# Daughter_Board.net
KiCad netlist of a schematic drawn in EAGLE
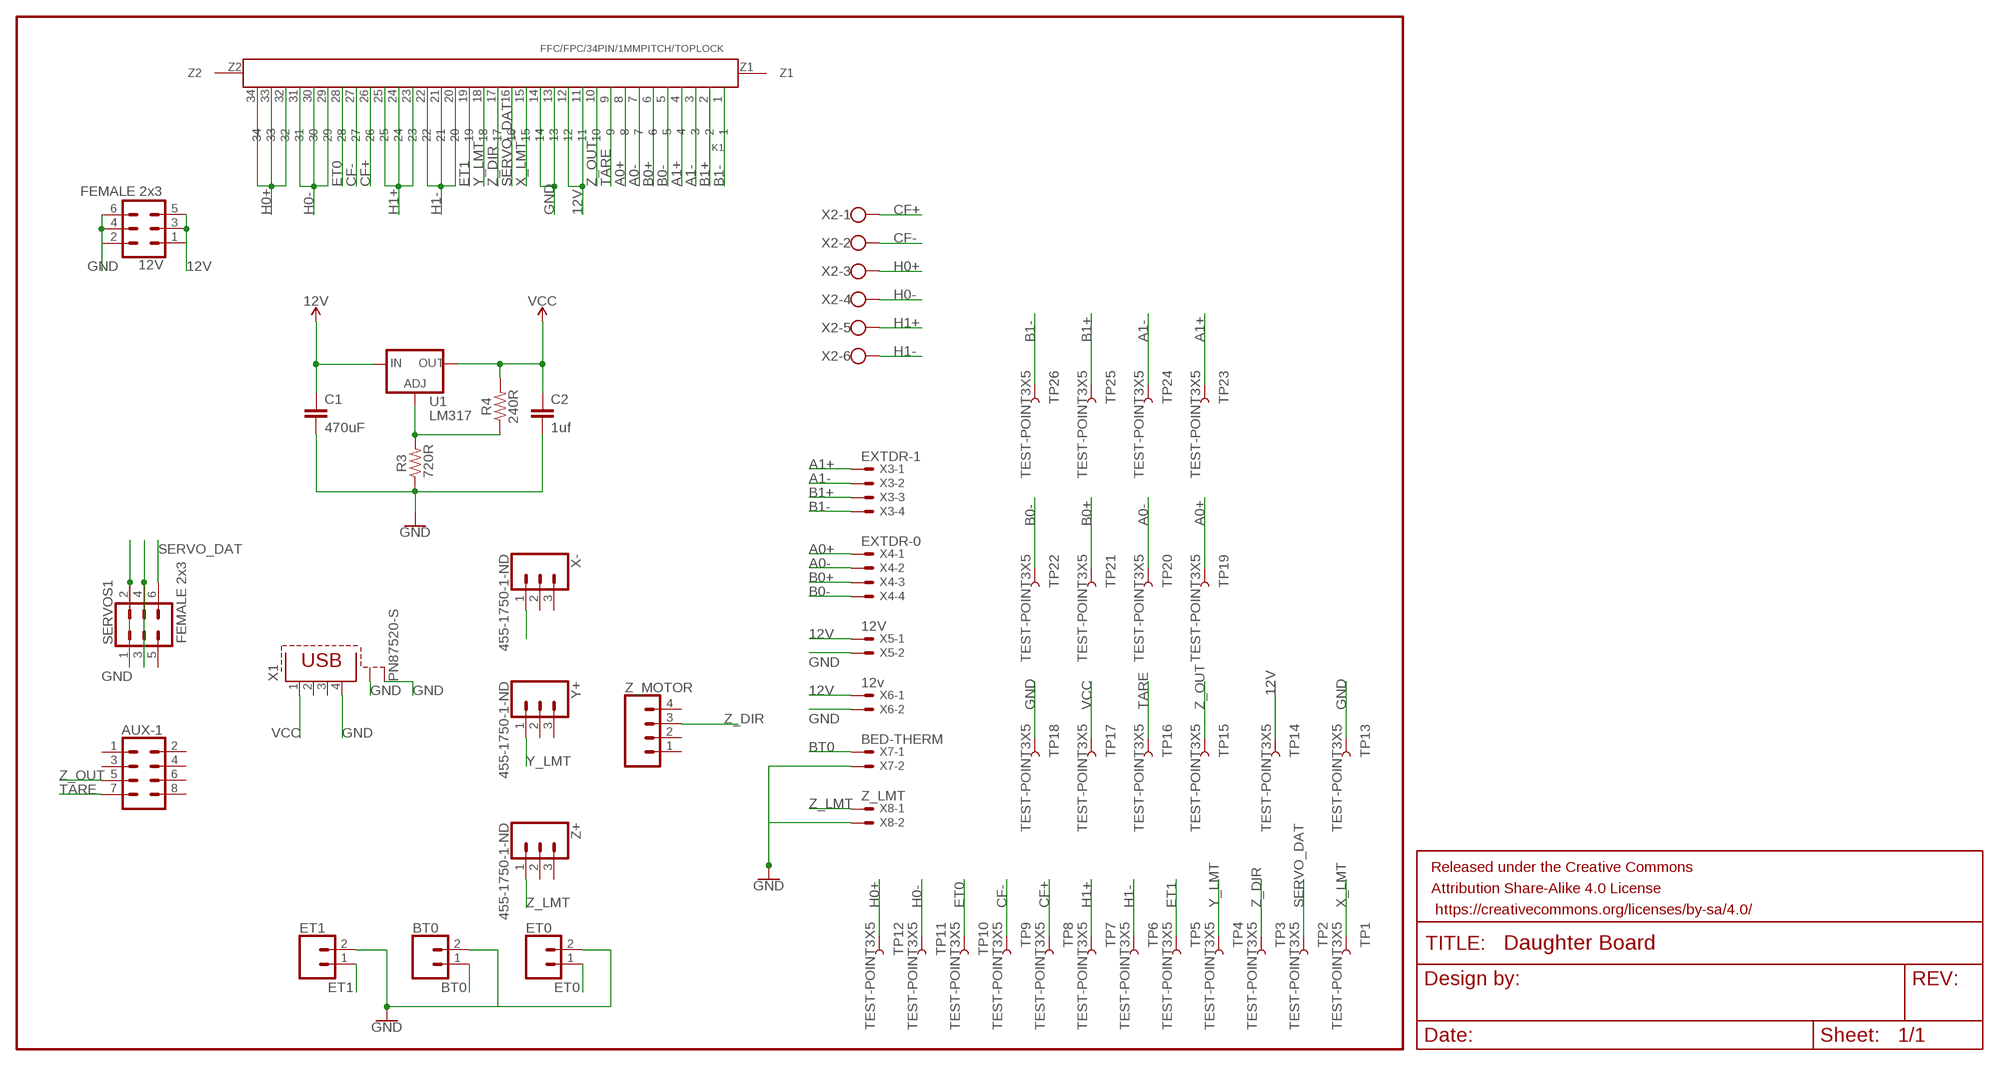
[diagram p0: schematic, sheet 1]

(export (version "E")
  (design (tool "Eeschema 10.0.6"))
  (components
    (comp (ref "12V")
      (value "FEMALE 2x3")
      (footprint "eagle-import:2X3")
      (libsource (lib "eagle-import") (part "CONN_03X2FEMALE"))
    )
    (comp (ref "AUX-1")
      (value "CONN_04X2")
      (footprint "eagle-import:2X4")
      (libsource (lib "eagle-import") (part "CONN_04X2"))
    )
    (comp (ref "BT0")
      (value "CONN_02")
      (footprint "eagle-import:1X02")
      (libsource (lib "eagle-import") (part "CONN_02"))
    )
    (comp (ref "C1")
      (value "470uF")
      (footprint "eagle-import:0603")
      (libsource (lib "eagle-import") (part "9.0PF-0603-50V-10%"))
    )
    (comp (ref "C2")
      (value "1uf")
      (footprint "eagle-import:0603")
      (libsource (lib "eagle-import") (part "9.0PF-0603-50V-10%"))
    )
    (comp (ref "ET0")
      (value "CONN_02")
      (footprint "eagle-import:1X02")
      (libsource (lib "eagle-import") (part "CONN_02"))
    )
    (comp (ref "ET1")
      (value "CONN_02")
      (footprint "eagle-import:1X02")
      (libsource (lib "eagle-import") (part "CONN_02"))
    )
    (comp (ref "FRAME1")
      (value "FRAME-LETTERNO_PACKAGE")
      (footprint "eagle-import:DUMMY")
      (fields (field (name "DESIGNER") "Nobody"))
      (libsource (lib "eagle-import") (part "FRAME-LETTERNO_PACKAGE"))
    )
    (comp (ref "K1")
      (value "FFC/FPC/34PIN/1MMPITCH/TOPLOCK")
      (footprint "eagle-import:34PIN_1MMPITCH_FFC_FPC")
      (libsource (lib "eagle-import") (part "FFC/FPC/34PIN/1MMPITCH/TOPLOCK"))
    )
    (comp (ref "R3")
      (value "720R")
      (footprint "eagle-import:0603")
      (libsource (lib "eagle-import") (part "RESISTOR0603"))
    )
    (comp (ref "R4")
      (value "240R")
      (footprint "eagle-import:0603")
      (libsource (lib "eagle-import") (part "RESISTOR0603"))
    )
    (comp (ref "SERVOS1")
      (value "FEMALE 2x3")
      (footprint "eagle-import:2X3")
      (libsource (lib "eagle-import") (part "CONN_03X2FEMALE"))
    )
    (comp (ref "TP1")
      (value "TEST-POINT3X5")
      (footprint "eagle-import:PAD.03X.05")
      (libsource (lib "eagle-import") (part "TEST-POINT3X5"))
    )
    (comp (ref "TP2")
      (value "TEST-POINT3X5")
      (footprint "eagle-import:PAD.03X.05")
      (libsource (lib "eagle-import") (part "TEST-POINT3X5"))
    )
    (comp (ref "TP3")
      (value "TEST-POINT3X5")
      (footprint "eagle-import:PAD.03X.05")
      (libsource (lib "eagle-import") (part "TEST-POINT3X5"))
    )
    (comp (ref "TP4")
      (value "TEST-POINT3X5")
      (footprint "eagle-import:PAD.03X.05")
      (libsource (lib "eagle-import") (part "TEST-POINT3X5"))
    )
    (comp (ref "TP5")
      (value "TEST-POINT3X5")
      (footprint "eagle-import:PAD.03X.05")
      (libsource (lib "eagle-import") (part "TEST-POINT3X5"))
    )
    (comp (ref "TP6")
      (value "TEST-POINT3X5")
      (footprint "eagle-import:PAD.03X.05")
      (libsource (lib "eagle-import") (part "TEST-POINT3X5"))
    )
    (comp (ref "TP7")
      (value "TEST-POINT3X5")
      (footprint "eagle-import:PAD.03X.05")
      (libsource (lib "eagle-import") (part "TEST-POINT3X5"))
    )
    (comp (ref "TP8")
      (value "TEST-POINT3X5")
      (footprint "eagle-import:PAD.03X.05")
      (libsource (lib "eagle-import") (part "TEST-POINT3X5"))
    )
    (comp (ref "TP9")
      (value "TEST-POINT3X5")
      (footprint "eagle-import:PAD.03X.05")
      (libsource (lib "eagle-import") (part "TEST-POINT3X5"))
    )
    (comp (ref "TP10")
      (value "TEST-POINT3X5")
      (footprint "eagle-import:PAD.03X.05")
      (libsource (lib "eagle-import") (part "TEST-POINT3X5"))
    )
    (comp (ref "TP11")
      (value "TEST-POINT3X5")
      (footprint "eagle-import:PAD.03X.05")
      (libsource (lib "eagle-import") (part "TEST-POINT3X5"))
    )
    (comp (ref "TP12")
      (value "TEST-POINT3X5")
      (footprint "eagle-import:PAD.03X.05")
      (libsource (lib "eagle-import") (part "TEST-POINT3X5"))
    )
    (comp (ref "TP13")
      (value "TEST-POINT3X5")
      (footprint "eagle-import:PAD.03X.05")
      (libsource (lib "eagle-import") (part "TEST-POINT3X5"))
    )
    (comp (ref "TP14")
      (value "TEST-POINT3X5")
      (footprint "eagle-import:PAD.03X.05")
      (libsource (lib "eagle-import") (part "TEST-POINT3X5"))
    )
    (comp (ref "TP15")
      (value "TEST-POINT3X5")
      (footprint "eagle-import:PAD.03X.05")
      (libsource (lib "eagle-import") (part "TEST-POINT3X5"))
    )
    (comp (ref "TP16")
      (value "TEST-POINT3X5")
      (footprint "eagle-import:PAD.03X.05")
      (libsource (lib "eagle-import") (part "TEST-POINT3X5"))
    )
    (comp (ref "TP17")
      (value "TEST-POINT3X5")
      (footprint "eagle-import:PAD.03X.05")
      (libsource (lib "eagle-import") (part "TEST-POINT3X5"))
    )
    (comp (ref "TP18")
      (value "TEST-POINT3X5")
      (footprint "eagle-import:PAD.03X.05")
      (libsource (lib "eagle-import") (part "TEST-POINT3X5"))
    )
    (comp (ref "TP19")
      (value "TEST-POINT3X5")
      (footprint "eagle-import:PAD.03X.05")
      (libsource (lib "eagle-import") (part "TEST-POINT3X5"))
    )
    (comp (ref "TP20")
      (value "TEST-POINT3X5")
      (footprint "eagle-import:PAD.03X.05")
      (libsource (lib "eagle-import") (part "TEST-POINT3X5"))
    )
    (comp (ref "TP21")
      (value "TEST-POINT3X5")
      (footprint "eagle-import:PAD.03X.05")
      (libsource (lib "eagle-import") (part "TEST-POINT3X5"))
    )
    (comp (ref "TP22")
      (value "TEST-POINT3X5")
      (footprint "eagle-import:PAD.03X.05")
      (libsource (lib "eagle-import") (part "TEST-POINT3X5"))
    )
    (comp (ref "TP23")
      (value "TEST-POINT3X5")
      (footprint "eagle-import:PAD.03X.05")
      (libsource (lib "eagle-import") (part "TEST-POINT3X5"))
    )
    (comp (ref "TP24")
      (value "TEST-POINT3X5")
      (footprint "eagle-import:PAD.03X.05")
      (libsource (lib "eagle-import") (part "TEST-POINT3X5"))
    )
    (comp (ref "TP25")
      (value "TEST-POINT3X5")
      (footprint "eagle-import:PAD.03X.05")
      (libsource (lib "eagle-import") (part "TEST-POINT3X5"))
    )
    (comp (ref "TP26")
      (value "TEST-POINT3X5")
      (footprint "eagle-import:PAD.03X.05")
      (libsource (lib "eagle-import") (part "TEST-POINT3X5"))
    )
    (comp (ref "U1")
      (value "LM317")
      (footprint "eagle-import:TO220-ADJ")
      (libsource (lib "eagle-import") (part "V_REG_317SINK"))
    )
    (comp (ref "X-")
      (value "455-1750-1-ND")
      (footprint "eagle-import:1X03")
      (libsource (lib "eagle-import") (part "CONN_03"))
    )
    (comp (ref "X1")
      (value "PN87520-S")
      (footprint "eagle-import:PN87520-S")
      (libsource (lib "eagle-import") (part "PN87520-S"))
    )
    (comp (ref "X2")
      (value "W237-6")
      (footprint "eagle-import:W237-6")
      (libsource (lib "eagle-import") (part "W237-6"))
    )
    (comp (ref "X3")
      (value "EXTDR-1")
      (footprint "eagle-import:JST-XH-04-PACKAGE-LONG-PAD")
      (libsource (lib "eagle-import") (part "JST-XH-04-PIN-LONG-PAD"))
    )
    (comp (ref "X4")
      (value "EXTDR-0")
      (footprint "eagle-import:JST-XH-04-PACKAGE-LONG-PAD")
      (libsource (lib "eagle-import") (part "JST-XH-04-PIN-LONG-PAD"))
    )
    (comp (ref "X5")
      (value "12V")
      (footprint "eagle-import:JST-XH-02-PACKAGE-LONG-PAD")
      (libsource (lib "eagle-import") (part "JST-XH-02-PIN-LONG-PAD"))
    )
    (comp (ref "X6")
      (value "12v")
      (footprint "eagle-import:JST-XH-02-PACKAGE-LONG-PAD")
      (libsource (lib "eagle-import") (part "JST-XH-02-PIN-LONG-PAD"))
    )
    (comp (ref "X7")
      (value "BED-THERM")
      (footprint "eagle-import:JST-XH-02-PACKAGE-LONG-PAD")
      (libsource (lib "eagle-import") (part "JST-XH-02-PIN-LONG-PAD"))
    )
    (comp (ref "X8")
      (value "Z_LMT")
      (footprint "eagle-import:JST-XH-02-PACKAGE-LONG-PAD")
      (libsource (lib "eagle-import") (part "JST-XH-02-PIN-LONG-PAD"))
    )
    (comp (ref "Y+")
      (value "455-1750-1-ND")
      (footprint "eagle-import:1X03")
      (libsource (lib "eagle-import") (part "CONN_03"))
    )
    (comp (ref "Z+")
      (value "455-1750-1-ND")
      (footprint "eagle-import:1X03")
      (libsource (lib "eagle-import") (part "CONN_03"))
    )
    (comp (ref "Z_MOTOR")
      (value "CONN_04")
      (footprint "eagle-import:1X04")
      (libsource (lib "eagle-import") (part "CONN_04"))
    )
  )
  (nets
    (net (code "1") (name "/A0+") (class "Default")
      (node (ref "K1") (pin "8") (pinfunction "8_8") (pintype "bidirectional"))
      (node (ref "TP19") (pin "P$1") (pinfunction "1_P$1") (pintype "bidirectional"))
      (node (ref "X4") (pin "1") (pinfunction "S_1") (pintype "passive"))
    )
    (net (code "2") (name "/A0-") (class "Default")
      (node (ref "K1") (pin "7") (pinfunction "7_7") (pintype "bidirectional"))
      (node (ref "TP20") (pin "P$1") (pinfunction "1_P$1") (pintype "bidirectional"))
      (node (ref "X4") (pin "2") (pinfunction "S_2") (pintype "passive"))
    )
    (net (code "3") (name "/A1+") (class "Default")
      (node (ref "K1") (pin "4") (pinfunction "4_4") (pintype "bidirectional"))
      (node (ref "TP23") (pin "P$1") (pinfunction "1_P$1") (pintype "bidirectional"))
      (node (ref "X3") (pin "1") (pinfunction "S_1") (pintype "passive"))
    )
    (net (code "4") (name "/A1-") (class "Default")
      (node (ref "K1") (pin "3") (pinfunction "3_3") (pintype "bidirectional"))
      (node (ref "TP24") (pin "P$1") (pinfunction "1_P$1") (pintype "bidirectional"))
      (node (ref "X3") (pin "2") (pinfunction "S_2") (pintype "passive"))
    )
    (net (code "5") (name "/B0+") (class "Default")
      (node (ref "K1") (pin "6") (pinfunction "6_6") (pintype "bidirectional"))
      (node (ref "TP21") (pin "P$1") (pinfunction "1_P$1") (pintype "bidirectional"))
      (node (ref "X4") (pin "3") (pinfunction "S_3") (pintype "passive"))
    )
    (net (code "6") (name "/B0-") (class "Default")
      (node (ref "K1") (pin "5") (pinfunction "5_5") (pintype "bidirectional"))
      (node (ref "TP22") (pin "P$1") (pinfunction "1_P$1") (pintype "bidirectional"))
      (node (ref "X4") (pin "4") (pinfunction "S_4") (pintype "passive"))
    )
    (net (code "7") (name "/B1+") (class "Default")
      (node (ref "K1") (pin "2") (pinfunction "2_2") (pintype "bidirectional"))
      (node (ref "TP25") (pin "P$1") (pinfunction "1_P$1") (pintype "bidirectional"))
      (node (ref "X3") (pin "3") (pinfunction "S_3") (pintype "passive"))
    )
    (net (code "8") (name "/B1-") (class "Default")
      (node (ref "K1") (pin "1") (pinfunction "1_1") (pintype "bidirectional"))
      (node (ref "TP26") (pin "P$1") (pinfunction "1_P$1") (pintype "bidirectional"))
      (node (ref "X3") (pin "4") (pinfunction "S_4") (pintype "passive"))
    )
    (net (code "9") (name "/BT0") (class "Default")
      (node (ref "BT0") (pin "1") (pinfunction "1_1") (pintype "passive"))
      (node (ref "X7") (pin "1") (pinfunction "S_1") (pintype "passive"))
    )
    (net (code "10") (name "/CF+") (class "Default")
      (node (ref "K1") (pin "26") (pinfunction "26_26") (pintype "bidirectional"))
      (node (ref "TP8") (pin "P$1") (pinfunction "1_P$1") (pintype "bidirectional"))
      (node (ref "X2") (pin "1") (pinfunction "KL_1") (pintype "passive"))
    )
    (net (code "11") (name "/CF-") (class "Default")
      (node (ref "K1") (pin "27") (pinfunction "27_27") (pintype "bidirectional"))
      (node (ref "TP9") (pin "P$1") (pinfunction "1_P$1") (pintype "bidirectional"))
      (node (ref "X2") (pin "2") (pinfunction "KL_2") (pintype "passive"))
    )
    (net (code "12") (name "/ET0") (class "Default")
      (node (ref "ET0") (pin "1") (pinfunction "1_1") (pintype "passive"))
      (node (ref "K1") (pin "28") (pinfunction "28_28") (pintype "bidirectional"))
      (node (ref "TP10") (pin "P$1") (pinfunction "1_P$1") (pintype "bidirectional"))
    )
    (net (code "13") (name "/ET1") (class "Default")
      (node (ref "ET1") (pin "1") (pinfunction "1_1") (pintype "passive"))
      (node (ref "K1") (pin "19") (pinfunction "19_19") (pintype "bidirectional"))
      (node (ref "TP5") (pin "P$1") (pinfunction "1_P$1") (pintype "bidirectional"))
    )
    (net (code "14") (name "/H0+") (class "Default")
      (node (ref "K1") (pin "32") (pinfunction "32_32") (pintype "bidirectional"))
      (node (ref "K1") (pin "33") (pinfunction "33_33") (pintype "bidirectional"))
      (node (ref "K1") (pin "34") (pinfunction "34_34") (pintype "bidirectional"))
      (node (ref "TP12") (pin "P$1") (pinfunction "1_P$1") (pintype "bidirectional"))
      (node (ref "X2") (pin "3") (pinfunction "KL_3") (pintype "passive"))
    )
    (net (code "15") (name "/H0-") (class "Default")
      (node (ref "K1") (pin "29") (pinfunction "29_29") (pintype "bidirectional"))
      (node (ref "K1") (pin "30") (pinfunction "30_30") (pintype "bidirectional"))
      (node (ref "K1") (pin "31") (pinfunction "31_31") (pintype "bidirectional"))
      (node (ref "TP11") (pin "P$1") (pinfunction "1_P$1") (pintype "bidirectional"))
      (node (ref "X2") (pin "4") (pinfunction "KL_4") (pintype "passive"))
    )
    (net (code "16") (name "/H1+") (class "Default")
      (node (ref "K1") (pin "23") (pinfunction "23_23") (pintype "bidirectional"))
      (node (ref "K1") (pin "24") (pinfunction "24_24") (pintype "bidirectional"))
      (node (ref "K1") (pin "25") (pinfunction "25_25") (pintype "bidirectional"))
      (node (ref "TP7") (pin "P$1") (pinfunction "1_P$1") (pintype "bidirectional"))
      (node (ref "X2") (pin "5") (pinfunction "KL_5") (pintype "passive"))
    )
    (net (code "17") (name "/H1-") (class "Default")
      (node (ref "K1") (pin "20") (pinfunction "20_20") (pintype "bidirectional"))
      (node (ref "K1") (pin "21") (pinfunction "21_21") (pintype "bidirectional"))
      (node (ref "K1") (pin "22") (pinfunction "22_22") (pintype "bidirectional"))
      (node (ref "TP6") (pin "P$1") (pinfunction "1_P$1") (pintype "bidirectional"))
      (node (ref "X2") (pin "6") (pinfunction "KL_6") (pintype "passive"))
    )
    (net (code "18") (name "/SERVO_DAT") (class "Default")
      (node (ref "K1") (pin "16") (pinfunction "16_16") (pintype "bidirectional"))
      (node (ref "SERVOS1") (pin "6") (pinfunction "6_6") (pintype "bidirectional"))
      (node (ref "TP2") (pin "P$1") (pinfunction "1_P$1") (pintype "bidirectional"))
    )
    (net (code "19") (name "/TARE") (class "Default")
      (node (ref "AUX-1") (pin "7") (pinfunction "7_7") (pintype "passive"))
      (node (ref "K1") (pin "9") (pinfunction "9_9") (pintype "bidirectional"))
      (node (ref "TP16") (pin "P$1") (pinfunction "1_P$1") (pintype "bidirectional"))
    )
    (net (code "20") (name "/X_LMT") (class "Default")
      (node (ref "K1") (pin "15") (pinfunction "15_15") (pintype "bidirectional"))
      (node (ref "TP1") (pin "P$1") (pinfunction "1_P$1") (pintype "bidirectional"))
      (node (ref "X-") (pin "1") (pinfunction "1_1") (pintype "passive"))
    )
    (net (code "21") (name "/Y_LMT") (class "Default")
      (node (ref "K1") (pin "18") (pinfunction "18_18") (pintype "bidirectional"))
      (node (ref "TP4") (pin "P$1") (pinfunction "1_P$1") (pintype "bidirectional"))
      (node (ref "Y+") (pin "1") (pinfunction "1_1") (pintype "passive"))
    )
    (net (code "22") (name "/Z_DIR") (class "Default")
      (node (ref "K1") (pin "17") (pinfunction "17_17") (pintype "bidirectional"))
      (node (ref "TP3") (pin "P$1") (pinfunction "1_P$1") (pintype "bidirectional"))
      (node (ref "Z_MOTOR") (pin "3") (pinfunction "3_3") (pintype "passive"))
    )
    (net (code "23") (name "/Z_LMT") (class "Default")
      (node (ref "X8") (pin "1") (pinfunction "S_1") (pintype "passive"))
      (node (ref "Z+") (pin "1") (pinfunction "1_1") (pintype "passive"))
    )
    (net (code "24") (name "/Z_OUT") (class "Default")
      (node (ref "AUX-1") (pin "5") (pinfunction "5_5") (pintype "passive"))
      (node (ref "K1") (pin "10") (pinfunction "10_10") (pintype "bidirectional"))
      (node (ref "TP15") (pin "P$1") (pinfunction "1_P$1") (pintype "bidirectional"))
    )
    (net (code "25") (name "12V") (class "Default")
      (node (ref "12V") (pin "1") (pinfunction "1_1") (pintype "bidirectional"))
      (node (ref "12V") (pin "3") (pinfunction "3_3") (pintype "bidirectional"))
      (node (ref "12V") (pin "5") (pinfunction "5_5") (pintype "bidirectional"))
      (node (ref "C1") (pin "1") (pinfunction "1_1") (pintype "passive"))
      (node (ref "K1") (pin "11") (pinfunction "11_11") (pintype "bidirectional"))
      (node (ref "K1") (pin "12") (pinfunction "12_12") (pintype "bidirectional"))
      (node (ref "TP14") (pin "P$1") (pinfunction "1_P$1") (pintype "bidirectional"))
      (node (ref "U1") (pin "IN") (pinfunction "IN_IN") (pintype "input"))
      (node (ref "X5") (pin "1") (pinfunction "S_1") (pintype "passive"))
      (node (ref "X6") (pin "1") (pinfunction "S_1") (pintype "passive"))
    )
    (net (code "26") (name "GND") (class "Default")
      (node (ref "12V") (pin "2") (pinfunction "2_2") (pintype "bidirectional"))
      (node (ref "12V") (pin "4") (pinfunction "4_4") (pintype "bidirectional"))
      (node (ref "12V") (pin "6") (pinfunction "6_6") (pintype "bidirectional"))
      (node (ref "BT0") (pin "2") (pinfunction "2_2") (pintype "passive"))
      (node (ref "C1") (pin "2") (pinfunction "2_2") (pintype "passive"))
      (node (ref "C2") (pin "2") (pinfunction "2_2") (pintype "passive"))
      (node (ref "ET0") (pin "2") (pinfunction "2_2") (pintype "passive"))
      (node (ref "ET1") (pin "2") (pinfunction "2_2") (pintype "passive"))
      (node (ref "K1") (pin "13") (pinfunction "13_13") (pintype "bidirectional"))
      (node (ref "K1") (pin "14") (pinfunction "14_14") (pintype "bidirectional"))
      (node (ref "R3") (pin "1") (pinfunction "1_1") (pintype "passive"))
      (node (ref "SERVOS1") (pin "1") (pinfunction "1_1") (pintype "bidirectional"))
      (node (ref "SERVOS1") (pin "2") (pinfunction "2_2") (pintype "bidirectional"))
      (node (ref "TP13") (pin "P$1") (pinfunction "1_P$1") (pintype "bidirectional"))
      (node (ref "TP18") (pin "P$1") (pinfunction "1_P$1") (pintype "bidirectional"))
      (node (ref "X1") (pin "4") (pinfunction "4_4") (pintype "passive"))
      (node (ref "X1") (pin "S1") (pinfunction "S1_S1") (pintype "passive"))
      (node (ref "X1") (pin "S2") (pinfunction "S2_S2") (pintype "passive"))
      (node (ref "X5") (pin "2") (pinfunction "S_2") (pintype "passive"))
      (node (ref "X6") (pin "2") (pinfunction "S_2") (pintype "passive"))
      (node (ref "X7") (pin "2") (pinfunction "S_2") (pintype "passive"))
      (node (ref "X8") (pin "2") (pinfunction "S_2") (pintype "passive"))
    )
    (net (code "27") (name "Net-(R3-Pad2)") (class "Default")
      (node (ref "R3") (pin "2") (pinfunction "2_2") (pintype "passive"))
      (node (ref "R4") (pin "1") (pinfunction "1_1") (pintype "passive"))
      (node (ref "U1") (pin "ADJ") (pinfunction "ADJ_ADJ") (pintype "input"))
    )
    (net (code "28") (name "Net-(SERVOS1-Pad3)") (class "Default")
      (node (ref "SERVOS1") (pin "3") (pinfunction "3_3") (pintype "bidirectional"))
      (node (ref "SERVOS1") (pin "4") (pinfunction "4_4") (pintype "bidirectional"))
    )
    (net (code "29") (name "VCC") (class "Default")
      (node (ref "C2") (pin "1") (pinfunction "1_1") (pintype "passive"))
      (node (ref "R4") (pin "2") (pinfunction "2_2") (pintype "passive"))
      (node (ref "TP17") (pin "P$1") (pinfunction "1_P$1") (pintype "bidirectional"))
      (node (ref "U1") (pin "OUT") (pinfunction "OUT_OUT") (pintype "output"))
      (node (ref "X1") (pin "1") (pinfunction "1_1") (pintype "passive"))
    )
    (net (code "30") (name "unconnected-(AUX-1-Pad1)") (class "Default")
      (node (ref "AUX-1") (pin "1") (pinfunction "1_1") (pintype "passive"))
    )
    (net (code "31") (name "unconnected-(AUX-1-Pad2)") (class "Default")
      (node (ref "AUX-1") (pin "2") (pinfunction "2_2") (pintype "passive"))
    )
    (net (code "32") (name "unconnected-(AUX-1-Pad3)") (class "Default")
      (node (ref "AUX-1") (pin "3") (pinfunction "3_3") (pintype "passive"))
    )
    (net (code "33") (name "unconnected-(AUX-1-Pad4)") (class "Default")
      (node (ref "AUX-1") (pin "4") (pinfunction "4_4") (pintype "passive"))
    )
    (net (code "34") (name "unconnected-(AUX-1-Pad6)") (class "Default")
      (node (ref "AUX-1") (pin "6") (pinfunction "6_6") (pintype "passive"))
    )
    (net (code "35") (name "unconnected-(AUX-1-Pad8)") (class "Default")
      (node (ref "AUX-1") (pin "8") (pinfunction "8_8") (pintype "passive"))
    )
    (net (code "36") (name "unconnected-(K1-PadZ1)") (class "Default")
      (node (ref "K1") (pin "Z1") (pinfunction "Z1_Z1") (pintype "bidirectional"))
    )
    (net (code "37") (name "unconnected-(K1-PadZ2)") (class "Default")
      (node (ref "K1") (pin "Z2") (pinfunction "Z2_Z2") (pintype "bidirectional"))
    )
    (net (code "38") (name "unconnected-(SERVOS1-Pad5)") (class "Default")
      (node (ref "SERVOS1") (pin "5") (pinfunction "5_5") (pintype "bidirectional"))
    )
    (net (code "39") (name "unconnected-(X--Pad2)") (class "Default")
      (node (ref "X-") (pin "2") (pinfunction "2_2") (pintype "passive"))
    )
    (net (code "40") (name "unconnected-(X--Pad3)") (class "Default")
      (node (ref "X-") (pin "3") (pinfunction "3_3") (pintype "passive"))
    )
    (net (code "41") (name "unconnected-(X1-Pad2)") (class "Default")
      (node (ref "X1") (pin "2") (pinfunction "2_2") (pintype "passive"))
    )
    (net (code "42") (name "unconnected-(X1-Pad3)") (class "Default")
      (node (ref "X1") (pin "3") (pinfunction "3_3") (pintype "passive"))
    )
    (net (code "43") (name "unconnected-(Y+-Pad2)") (class "Default")
      (node (ref "Y+") (pin "2") (pinfunction "2_2") (pintype "passive"))
    )
    (net (code "44") (name "unconnected-(Y+-Pad3)") (class "Default")
      (node (ref "Y+") (pin "3") (pinfunction "3_3") (pintype "passive"))
    )
    (net (code "45") (name "unconnected-(Z+-Pad2)") (class "Default")
      (node (ref "Z+") (pin "2") (pinfunction "2_2") (pintype "passive"))
    )
    (net (code "46") (name "unconnected-(Z+-Pad3)") (class "Default")
      (node (ref "Z+") (pin "3") (pinfunction "3_3") (pintype "passive"))
    )
    (net (code "47") (name "unconnected-(Z_MOTOR-Pad1)") (class "Default")
      (node (ref "Z_MOTOR") (pin "1") (pinfunction "1_1") (pintype "passive"))
    )
    (net (code "48") (name "unconnected-(Z_MOTOR-Pad2)") (class "Default")
      (node (ref "Z_MOTOR") (pin "2") (pinfunction "2_2") (pintype "passive"))
    )
    (net (code "49") (name "unconnected-(Z_MOTOR-Pad4)") (class "Default")
      (node (ref "Z_MOTOR") (pin "4") (pinfunction "4_4") (pintype "passive"))
    )
  )
)
